# wrist_-_source.net
KiCad netlist of a schematic drawn in EAGLE
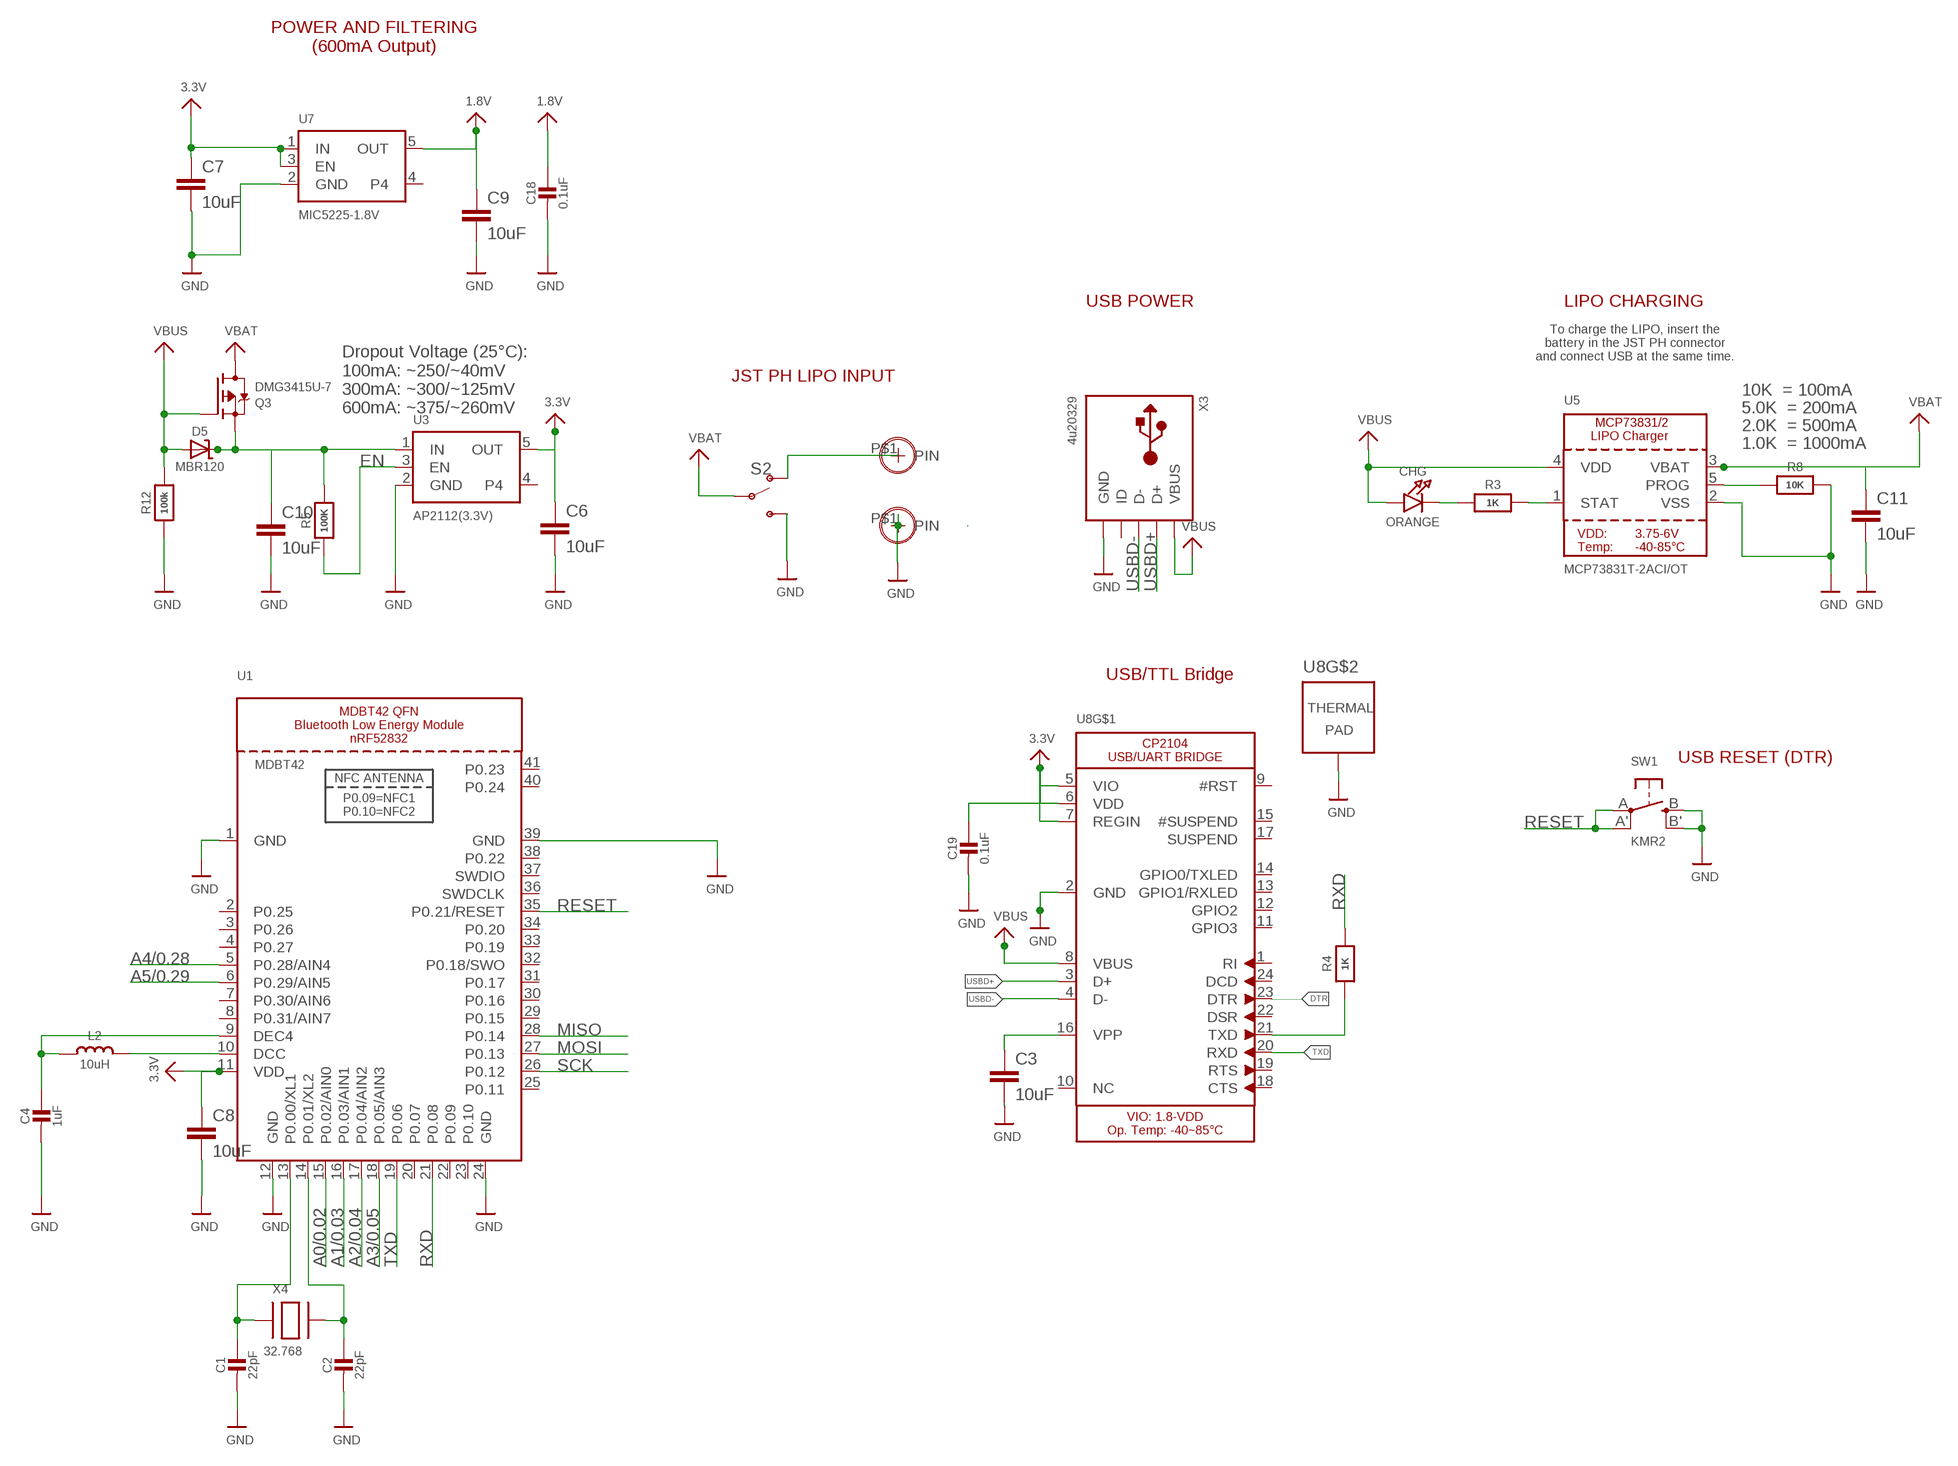
[diagram p0: schematic, sheet 1, part 1 of 2]
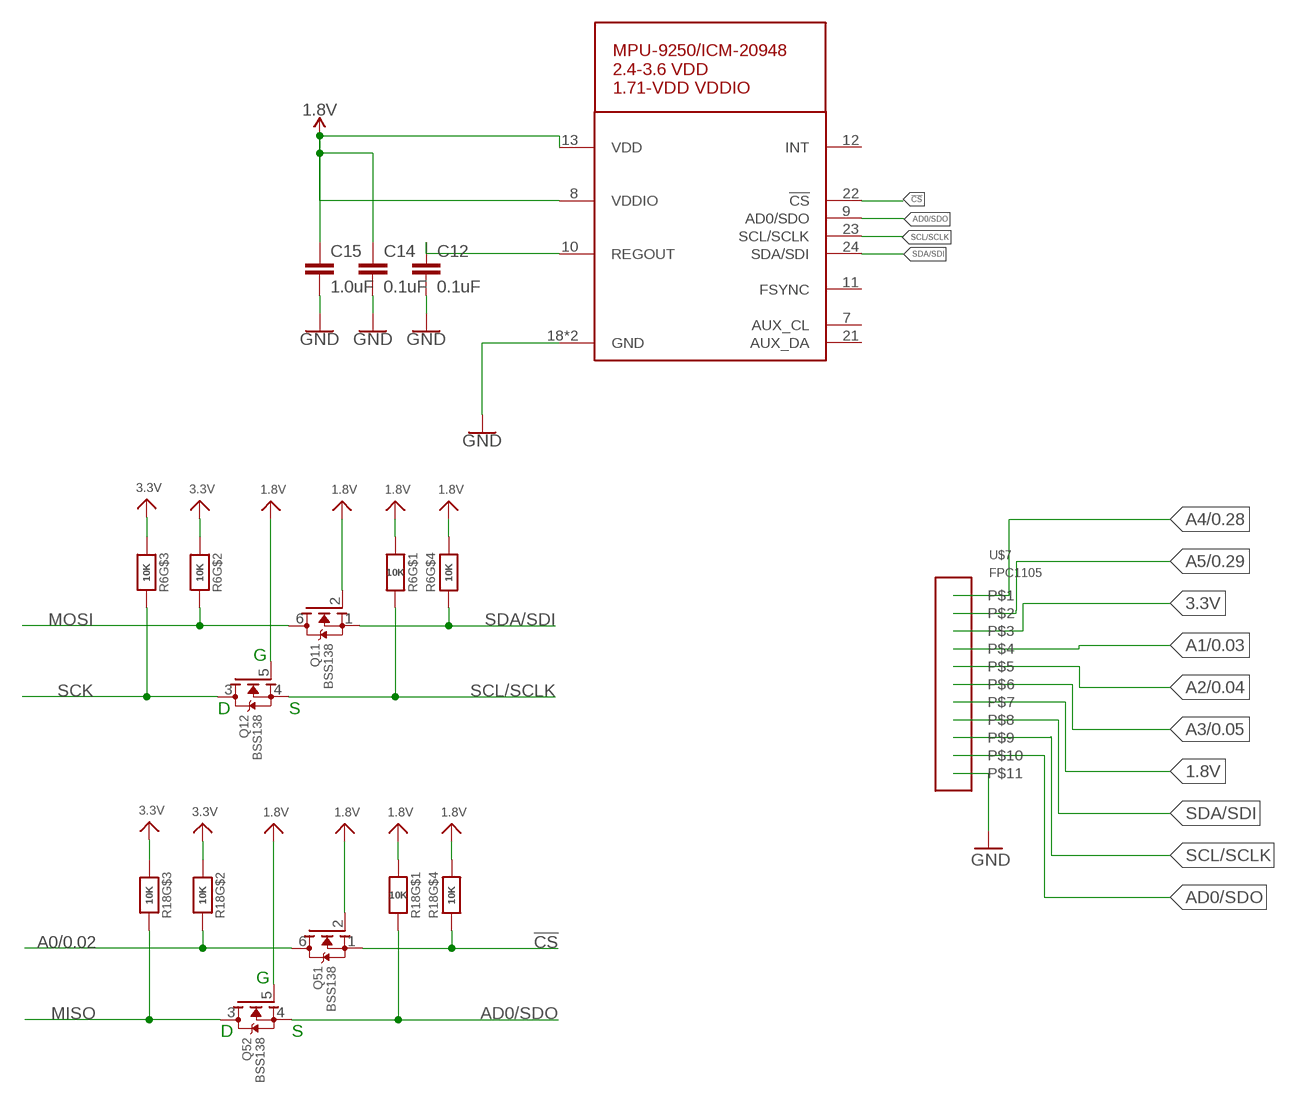
[diagram p1: schematic, sheet 1, part 2 of 2]

(export (version "E")
  (design (tool "Eeschema 10.0.6"))
  (components
    (comp (ref "C1")
      (value "22pF")
      (footprint "eagle-import:0603-NO")
      (libsource (lib "eagle-import") (part "CAP_CERAMIC0603_NO"))
    )
    (comp (ref "C2")
      (value "22pF")
      (footprint "eagle-import:0603-NO")
      (libsource (lib "eagle-import") (part "CAP_CERAMIC0603_NO"))
    )
    (comp (ref "C3")
      (value "10uF")
      (footprint "eagle-import:C0603")
      (libsource (lib "eagle-import") (part "C-EUC0603"))
    )
    (comp (ref "C4")
      (value "1uF")
      (footprint "eagle-import:0603-NO")
      (libsource (lib "eagle-import") (part "CAP_CERAMIC0603_NO"))
    )
    (comp (ref "C6")
      (value "10uF")
      (footprint "eagle-import:C0603")
      (libsource (lib "eagle-import") (part "C-EUC0603"))
    )
    (comp (ref "C7")
      (value "10uF")
      (footprint "eagle-import:C0603")
      (libsource (lib "eagle-import") (part "C-EUC0603"))
    )
    (comp (ref "C8")
      (value "10uF")
      (footprint "eagle-import:C0603")
      (libsource (lib "eagle-import") (part "C-EUC0603"))
    )
    (comp (ref "C9")
      (value "10uF")
      (footprint "eagle-import:C0603")
      (libsource (lib "eagle-import") (part "C-EUC0603"))
    )
    (comp (ref "C10")
      (value "10uF")
      (footprint "eagle-import:C0603")
      (libsource (lib "eagle-import") (part "C-EUC0603"))
    )
    (comp (ref "C11")
      (value "10uF")
      (footprint "eagle-import:C0603")
      (libsource (lib "eagle-import") (part "C-EUC0603"))
    )
    (comp (ref "C12")
      (value "0.1uF")
      (footprint "eagle-import:0603")
      (libsource (lib "eagle-import") (part "0.1UF-0603-25V-5%"))
    )
    (comp (ref "C14")
      (value "0.1uF")
      (footprint "eagle-import:0603")
      (libsource (lib "eagle-import") (part "0.1UF-0603-25V-5%"))
    )
    (comp (ref "C15")
      (value "1.0uF")
      (footprint "eagle-import:0603")
      (libsource (lib "eagle-import") (part "1.0UF-0603-16V-10%-X7R"))
    )
    (comp (ref "C18")
      (value "0.1uF")
      (footprint "eagle-import:0603-NO")
      (libsource (lib "eagle-import") (part "CAP_CERAMIC0603_NO"))
    )
    (comp (ref "C19")
      (value "0.1uF")
      (footprint "eagle-import:0603-NO")
      (libsource (lib "eagle-import") (part "CAP_CERAMIC0603_NO"))
    )
    (comp (ref "CHG")
      (value "ORANGE")
      (footprint "eagle-import:CHIPLED_0805_NOOUTLINE")
      (libsource (lib "eagle-import") (part "LED0805_NOOUTLINE"))
    )
    (comp (ref "D5")
      (value "MBR120")
      (footprint "eagle-import:SOD-123")
      (libsource (lib "eagle-import") (part "DIODE-SCHOTTKYSOD-123"))
    )
    (comp (ref "IC1")
      (value "ADAFRUIT_SENSOR_MPU-9250_ICM20948")
      (footprint "eagle-import:ADAFRUIT_SENSOR_QFN24_3MM_NOEP")
      (libsource (lib "eagle-import") (part "ADAFRUIT_SENSOR_MPU-9250_ICM20948"))
    )
    (comp (ref "L2")
      (value "10uH")
      (footprint "eagle-import:0805-NO")
      (libsource (lib "eagle-import") (part "INDUCTOR0805-NO"))
    )
    (comp (ref "Q1")
      (value "BSS138")
      (footprint "eagle-import:SOT363")
      (libsource (lib "eagle-import") (part "MOSFET-N_DUAL"))
    )
    (comp (ref "Q3")
      (value "DMG3415U-7")
      (footprint "eagle-import:SOT23-R")
      (libsource (lib "eagle-import") (part "MOSFET-P"))
    )
    (comp (ref "Q5")
      (value "BSS138")
      (footprint "eagle-import:SOT363")
      (libsource (lib "eagle-import") (part "MOSFET-N_DUAL"))
    )
    (comp (ref "R3")
      (value "1K")
      (footprint "eagle-import:0603-NO")
      (libsource (lib "eagle-import") (part "RESISTOR_0603_NOOUT"))
    )
    (comp (ref "R4")
      (value "1K")
      (footprint "eagle-import:0603-NO")
      (libsource (lib "eagle-import") (part "RESISTOR_0603_NOOUT"))
    )
    (comp (ref "R5")
      (value "100K")
      (footprint "eagle-import:0603-NO")
      (libsource (lib "eagle-import") (part "RESISTOR_0603_NOOUT"))
    )
    (comp (ref "R6")
      (value "10K")
      (footprint "eagle-import:RESPACK_4X0603")
      (libsource (lib "eagle-import") (part "RESISTOR_4PACK"))
    )
    (comp (ref "R8")
      (value "10K")
      (footprint "eagle-import:0603-NO")
      (libsource (lib "eagle-import") (part "RESISTOR_0603_NOOUT"))
    )
    (comp (ref "R12")
      (value "100k")
      (footprint "eagle-import:0603-NO")
      (libsource (lib "eagle-import") (part "RESISTOR_0603_NOOUT"))
    )
    (comp (ref "R18")
      (value "10K")
      (footprint "eagle-import:RESPACK_4X0603")
      (libsource (lib "eagle-import") (part "RESISTOR_4PACK"))
    )
    (comp (ref "S2")
      (value "SWITCH-SPDT-SMD-RIGHT-ANGLE")
      (footprint "eagle-import:SWITCH_SPST_SMD_A")
      (libsource (lib "eagle-import") (part "SWITCH-SPDT-SMD-RIGHT-ANGLE"))
    )
    (comp (ref "SW1")
      (value "KMR2")
      (footprint "eagle-import:BTN_KMR2_4.6X2.8")
      (libsource (lib "eagle-import") (part "SWITCH_TACT_SMT4.6X2.8"))
    )
    (comp (ref "U$7")
      (value "FPC1105")
      (footprint "eagle-import:FPC1105")
      (libsource (lib "eagle-import") (part "FPC1105"))
    )
    (comp (ref "U$9")
      (value "M3-HOLE_M0.9-HOLE0.9MM")
      (footprint "eagle-import:M3-HOLE_M0.9-HOLE")
      (libsource (lib "eagle-import") (part "M3-HOLE_M0.9-HOLE0.9MM"))
    )
    (comp (ref "U$13")
      (value "M3-HOLE_M0.9-HOLE0.9MM")
      (footprint "eagle-import:M3-HOLE_M0.9-HOLE")
      (libsource (lib "eagle-import") (part "M3-HOLE_M0.9-HOLE0.9MM"))
    )
    (comp (ref "U1")
      (value "MDBT42")
      (footprint "eagle-import:BLE_MODULE_RAYTAC_MDBT42")
      (libsource (lib "eagle-import") (part "NRF52832_MODULE_MDBT42"))
    )
    (comp (ref "U3")
      (value "AP2112(3.3V)")
      (footprint "eagle-import:SOT23-5")
      (libsource (lib "eagle-import") (part "VREG_SOT23-5"))
    )
    (comp (ref "U5")
      (value "MCP73831T-2ACI/OT")
      (footprint "eagle-import:SOT23-5")
      (libsource (lib "eagle-import") (part "MCP73831/2"))
    )
    (comp (ref "U7")
      (value "MIC5225-1.8V")
      (footprint "eagle-import:SOT23-5")
      (libsource (lib "eagle-import") (part "VREG_SOT23-5"))
    )
    (comp (ref "U8")
      (value "MICROBUILDER_CP2104")
      (footprint "eagle-import:MICROBUILDER_QFN24_4MM_SMSC")
      (libsource (lib "eagle-import") (part "MICROBUILDER_CP2104"))
    )
    (comp (ref "X3")
      (value "4u20329")
      (footprint "eagle-import:4UCONN_20329_V2")
      (libsource (lib "eagle-import") (part "USB_MICRO_20329_V2"))
    )
    (comp (ref "X4")
      (value "32.768")
      (footprint "eagle-import:XTAL3215")
      (libsource (lib "eagle-import") (part "XTAL-3.2X1.5"))
    )
  )
  (nets
    (net (code "1") (name "/A0{slash}0.02") (class "Default")
      (node (ref "Q5") (pin "6") (pinfunction "D_6") (pintype "bidirectional"))
      (node (ref "R18") (pin "7") (pinfunction "2_7") (pintype "passive"))
      (node (ref "U1") (pin "15") (pinfunction "P0.02/AIN0_15") (pintype "bidirectional"))
    )
    (net (code "2") (name "/EN") (class "Default")
      (node (ref "R5") (pin "1") (pinfunction "1_1") (pintype "passive"))
      (node (ref "U3") (pin "3") (pinfunction "EN_3") (pintype "input"))
    )
    (net (code "3") (name "/MISO") (class "Default")
      (node (ref "Q5") (pin "3") (pinfunction "D_3") (pintype "bidirectional"))
      (node (ref "R18") (pin "6") (pinfunction "2_6") (pintype "passive"))
      (node (ref "U1") (pin "28") (pinfunction "P0.14_28") (pintype "bidirectional"))
    )
    (net (code "4") (name "/MOSI") (class "Default")
      (node (ref "Q1") (pin "6") (pinfunction "D_6") (pintype "bidirectional"))
      (node (ref "R6") (pin "7") (pinfunction "2_7") (pintype "passive"))
      (node (ref "U1") (pin "27") (pinfunction "P0.13_27") (pintype "bidirectional"))
    )
    (net (code "5") (name "/RESET") (class "Default")
      (node (ref "SW1") (pin "A") (pinfunction "P_A") (pintype "passive"))
      (node (ref "SW1") (pin "A'") (pinfunction "P1_A'") (pintype "passive"))
      (node (ref "U1") (pin "35") (pinfunction "P0.21/RESET_35") (pintype "bidirectional"))
    )
    (net (code "6") (name "/RXD") (class "Default")
      (node (ref "R4") (pin "2") (pinfunction "2_2") (pintype "passive"))
      (node (ref "U1") (pin "21") (pinfunction "P0.08_21") (pintype "bidirectional"))
    )
    (net (code "7") (name "/SCK") (class "Default")
      (node (ref "Q1") (pin "3") (pinfunction "D_3") (pintype "bidirectional"))
      (node (ref "R6") (pin "6") (pinfunction "2_6") (pintype "passive"))
      (node (ref "U1") (pin "26") (pinfunction "P0.12_26") (pintype "bidirectional"))
    )
    (net (code "8") (name "/~{CS}") (class "Default")
      (node (ref "IC1") (pin "22") (pinfunction "~{CS}_22") (pintype "bidirectional"))
      (node (ref "Q5") (pin "1") (pinfunction "S_1") (pintype "bidirectional"))
      (node (ref "R18") (pin "5") (pinfunction "2_5") (pintype "passive"))
    )
    (net (code "9") (name "1.8V") (class "Default")
      (node (ref "C14") (pin "1") (pinfunction "1_1") (pintype "passive"))
      (node (ref "C15") (pin "1") (pinfunction "1_1") (pintype "passive"))
      (node (ref "C18") (pin "1") (pinfunction "1_1") (pintype "passive"))
      (node (ref "C9") (pin "1") (pinfunction "1_1") (pintype "passive"))
      (node (ref "IC1") (pin "13") (pinfunction "VDD_13") (pintype "bidirectional"))
      (node (ref "IC1") (pin "8") (pinfunction "VDDIO_8") (pintype "bidirectional"))
      (node (ref "Q1") (pin "2") (pinfunction "G_2") (pintype "bidirectional"))
      (node (ref "Q1") (pin "5") (pinfunction "G_5") (pintype "bidirectional"))
      (node (ref "Q5") (pin "2") (pinfunction "G_2") (pintype "bidirectional"))
      (node (ref "Q5") (pin "5") (pinfunction "G_5") (pintype "bidirectional"))
      (node (ref "R18") (pin "4") (pinfunction "1_4") (pintype "passive"))
      (node (ref "R18") (pin "8") (pinfunction "2_8") (pintype "passive"))
      (node (ref "R6") (pin "4") (pinfunction "1_4") (pintype "passive"))
      (node (ref "R6") (pin "8") (pinfunction "2_8") (pintype "passive"))
      (node (ref "U$7") (pin "P$7") (pinfunction "P$7_P$7") (pintype "bidirectional"))
      (node (ref "U7") (pin "5") (pinfunction "OUT_5") (pintype "power_in"))
    )
    (net (code "10") (name "3.3V") (class "Default")
      (node (ref "C19") (pin "1") (pinfunction "1_1") (pintype "passive"))
      (node (ref "C6") (pin "1") (pinfunction "1_1") (pintype "passive"))
      (node (ref "C7") (pin "1") (pinfunction "1_1") (pintype "passive"))
      (node (ref "C8") (pin "1") (pinfunction "1_1") (pintype "passive"))
      (node (ref "R18") (pin "2") (pinfunction "1_2") (pintype "passive"))
      (node (ref "R18") (pin "3") (pinfunction "1_3") (pintype "passive"))
      (node (ref "R6") (pin "2") (pinfunction "1_2") (pintype "passive"))
      (node (ref "R6") (pin "3") (pinfunction "1_3") (pintype "passive"))
      (node (ref "U$7") (pin "P$3") (pinfunction "P$3_P$3") (pintype "bidirectional"))
      (node (ref "U1") (pin "11") (pinfunction "VDD_11") (pintype "bidirectional"))
      (node (ref "U3") (pin "5") (pinfunction "OUT_5") (pintype "power_in"))
      (node (ref "U7") (pin "1") (pinfunction "IN_1") (pintype "power_in"))
      (node (ref "U7") (pin "3") (pinfunction "EN_3") (pintype "input"))
      (node (ref "U8") (pin "5") (pinfunction "VIO_5") (pintype "power_in"))
      (node (ref "U8") (pin "6") (pinfunction "VDD_6") (pintype "power_in"))
      (node (ref "U8") (pin "7") (pinfunction "REGIN_7") (pintype "power_in"))
    )
    (net (code "11") (name "A1{slash}0.03") (class "Default")
      (node (ref "U$7") (pin "P$4") (pinfunction "P$4_P$4") (pintype "bidirectional"))
      (node (ref "U1") (pin "16") (pinfunction "P0.03/AIN1_16") (pintype "bidirectional"))
    )
    (net (code "12") (name "A2{slash}0.04") (class "Default")
      (node (ref "U$7") (pin "P$5") (pinfunction "P$5_P$5") (pintype "bidirectional"))
      (node (ref "U1") (pin "17") (pinfunction "P0.04/AIN2_17") (pintype "bidirectional"))
    )
    (net (code "13") (name "A3{slash}0.05") (class "Default")
      (node (ref "U$7") (pin "P$6") (pinfunction "P$6_P$6") (pintype "bidirectional"))
      (node (ref "U1") (pin "18") (pinfunction "P0.05/AIN3_18") (pintype "bidirectional"))
    )
    (net (code "14") (name "A4{slash}0.28") (class "Default")
      (node (ref "U$7") (pin "P$1") (pinfunction "P$1_P$1") (pintype "bidirectional"))
      (node (ref "U1") (pin "5") (pinfunction "P0.28/AIN4_5") (pintype "bidirectional"))
    )
    (net (code "15") (name "A5{slash}0.29") (class "Default")
      (node (ref "U$7") (pin "P$2") (pinfunction "P$2_P$2") (pintype "bidirectional"))
      (node (ref "U1") (pin "6") (pinfunction "P0.29/AIN5_6") (pintype "bidirectional"))
    )
    (net (code "16") (name "AD0{slash}SDO") (class "Default")
      (node (ref "IC1") (pin "9") (pinfunction "AD0/SDO_9") (pintype "bidirectional"))
      (node (ref "Q5") (pin "4") (pinfunction "S_4") (pintype "bidirectional"))
      (node (ref "R18") (pin "1") (pinfunction "1_1") (pintype "passive"))
      (node (ref "U$7") (pin "P$10") (pinfunction "P$10_P$10") (pintype "bidirectional"))
    )
    (net (code "17") (name "DTR") (class "Default")
      (node (ref "U8") (pin "23") (pinfunction "DTR_23") (pintype "output"))
    )
    (net (code "18") (name "GND") (class "Default")
      (node (ref "C1") (pin "2") (pinfunction "2_2") (pintype "passive"))
      (node (ref "C10") (pin "2") (pinfunction "2_2") (pintype "passive"))
      (node (ref "C11") (pin "2") (pinfunction "2_2") (pintype "passive"))
      (node (ref "C12") (pin "2") (pinfunction "2_2") (pintype "passive"))
      (node (ref "C14") (pin "2") (pinfunction "2_2") (pintype "passive"))
      (node (ref "C15") (pin "2") (pinfunction "2_2") (pintype "passive"))
      (node (ref "C18") (pin "2") (pinfunction "2_2") (pintype "passive"))
      (node (ref "C19") (pin "2") (pinfunction "2_2") (pintype "passive"))
      (node (ref "C2") (pin "2") (pinfunction "2_2") (pintype "passive"))
      (node (ref "C3") (pin "2") (pinfunction "2_2") (pintype "passive"))
      (node (ref "C4") (pin "2") (pinfunction "2_2") (pintype "passive"))
      (node (ref "C6") (pin "2") (pinfunction "2_2") (pintype "passive"))
      (node (ref "C7") (pin "2") (pinfunction "2_2") (pintype "passive"))
      (node (ref "C8") (pin "2") (pinfunction "2_2") (pintype "passive"))
      (node (ref "C9") (pin "2") (pinfunction "2_2") (pintype "passive"))
      (node (ref "IC1") (pin "18") (pinfunction "GND_18") (pintype "bidirectional"))
      (node (ref "IC1") (pin "20") (pinfunction "GND_20") (pintype "bidirectional"))
      (node (ref "R12") (pin "1") (pinfunction "1_1") (pintype "passive"))
      (node (ref "R8") (pin "2") (pinfunction "2_2") (pintype "passive"))
      (node (ref "S2") (pin "3") (pinfunction "S_3") (pintype "passive"))
      (node (ref "SW1") (pin "B") (pinfunction "S_B") (pintype "passive"))
      (node (ref "SW1") (pin "B'") (pinfunction "S1_B'") (pintype "passive"))
      (node (ref "U$13") (pin "P$1") (pinfunction "PIN_P$1") (pintype "bidirectional"))
      (node (ref "U$7") (pin "P$11") (pinfunction "P$11_P$11") (pintype "bidirectional"))
      (node (ref "U1") (pin "1") (pinfunction "GND_1") (pintype "bidirectional"))
      (node (ref "U1") (pin "12") (pinfunction "GND_12") (pintype "bidirectional"))
      (node (ref "U1") (pin "24") (pinfunction "GND_24") (pintype "bidirectional"))
      (node (ref "U1") (pin "39") (pinfunction "GND_39") (pintype "bidirectional"))
      (node (ref "U3") (pin "2") (pinfunction "GND_2") (pintype "power_in"))
      (node (ref "U5") (pin "2") (pinfunction "VSS_2") (pintype "power_in"))
      (node (ref "U7") (pin "2") (pinfunction "GND_2") (pintype "power_in"))
      (node (ref "U8") (pin "2") (pinfunction "GND_2") (pintype "power_in"))
      (node (ref "U8") (pin "THERM") (pinfunction "TP_THERM") (pintype "power_in"))
      (node (ref "X3") (pin "BASE@1") (pinfunction "GND_BASE@1") (pintype "power_in"))
      (node (ref "X3") (pin "BASE@2") (pinfunction "GND_BASE@2") (pintype "power_in"))
      (node (ref "X3") (pin "GND") (pinfunction "GND_GND") (pintype "power_in"))
      (node (ref "X3") (pin "SPRT@1") (pinfunction "GND_SPRT@1") (pintype "power_in"))
      (node (ref "X3") (pin "SPRT@2") (pinfunction "GND_SPRT@2") (pintype "power_in"))
      (node (ref "X3") (pin "SPRT@3") (pinfunction "GND_SPRT@3") (pintype "power_in"))
      (node (ref "X3") (pin "SPRT@4") (pinfunction "GND_SPRT@4") (pintype "power_in"))
    )
    (net (code "19") (name "Net-(CHG-PadC)") (class "Default")
      (node (ref "CHG") (pin "C") (pinfunction "C_C") (pintype "passive"))
      (node (ref "R3") (pin "1") (pinfunction "1_1") (pintype "passive"))
    )
    (net (code "20") (name "Net-(IC1-REGOUT)") (class "Default")
      (node (ref "C12") (pin "1") (pinfunction "1_1") (pintype "passive"))
      (node (ref "IC1") (pin "10") (pinfunction "REGOUT_10") (pintype "bidirectional"))
    )
    (net (code "21") (name "Net-(Q3-S)") (class "Default")
      (node (ref "C10") (pin "1") (pinfunction "1_1") (pintype "passive"))
      (node (ref "D5") (pin "C") (pinfunction "C_C") (pintype "passive"))
      (node (ref "Q3") (pin "2") (pinfunction "S_2") (pintype "passive"))
      (node (ref "R5") (pin "2") (pinfunction "2_2") (pintype "passive"))
      (node (ref "U3") (pin "1") (pinfunction "IN_1") (pintype "power_in"))
    )
    (net (code "22") (name "Net-(S2-O)") (class "Default")
      (node (ref "S2") (pin "1") (pinfunction "O_1") (pintype "passive"))
      (node (ref "U$9") (pin "P$1") (pinfunction "PIN_P$1") (pintype "bidirectional"))
    )
    (net (code "23") (name "Net-(U1-DCC)") (class "Default")
      (node (ref "L2") (pin "2") (pinfunction "2_2") (pintype "passive"))
      (node (ref "U1") (pin "10") (pinfunction "DCC_10") (pintype "bidirectional"))
    )
    (net (code "24") (name "Net-(U1-DEC4)") (class "Default")
      (node (ref "C4") (pin "1") (pinfunction "1_1") (pintype "passive"))
      (node (ref "L2") (pin "1") (pinfunction "1_1") (pintype "passive"))
      (node (ref "U1") (pin "9") (pinfunction "DEC4_9") (pintype "bidirectional"))
    )
    (net (code "25") (name "Net-(U1-P0.00{slash}XL1)") (class "Default")
      (node (ref "C1") (pin "1") (pinfunction "1_1") (pintype "passive"))
      (node (ref "U1") (pin "13") (pinfunction "P0.00/XL1_13") (pintype "bidirectional"))
      (node (ref "X4") (pin "P$1") (pinfunction "P$1_P$1") (pintype "bidirectional"))
    )
    (net (code "26") (name "Net-(U1-P0.01{slash}XL2)") (class "Default")
      (node (ref "C2") (pin "1") (pinfunction "1_1") (pintype "passive"))
      (node (ref "U1") (pin "14") (pinfunction "P0.01/XL2_14") (pintype "bidirectional"))
      (node (ref "X4") (pin "P$2") (pinfunction "P$2_P$2") (pintype "bidirectional"))
    )
    (net (code "27") (name "Net-(U5-PROG)") (class "Default")
      (node (ref "R8") (pin "1") (pinfunction "1_1") (pintype "passive"))
      (node (ref "U5") (pin "5") (pinfunction "PROG_5") (pintype "input"))
    )
    (net (code "28") (name "Net-(U5-STAT)") (class "Default")
      (node (ref "R3") (pin "2") (pinfunction "2_2") (pintype "passive"))
      (node (ref "U5") (pin "1") (pinfunction "STAT_1") (pintype "output"))
    )
    (net (code "29") (name "Net-(U8A-TXD)") (class "Default")
      (node (ref "R4") (pin "1") (pinfunction "1_1") (pintype "passive"))
      (node (ref "U8") (pin "21") (pinfunction "TXD_21") (pintype "output"))
    )
    (net (code "30") (name "Net-(U8A-VPP)") (class "Default")
      (node (ref "C3") (pin "1") (pinfunction "1_1") (pintype "passive"))
      (node (ref "U8") (pin "16") (pinfunction "VPP_16") (pintype "bidirectional"))
    )
    (net (code "31") (name "SCL{slash}SCLK") (class "Default")
      (node (ref "IC1") (pin "23") (pinfunction "SCL/SCLK_23") (pintype "bidirectional"))
      (node (ref "Q1") (pin "4") (pinfunction "S_4") (pintype "bidirectional"))
      (node (ref "R6") (pin "1") (pinfunction "1_1") (pintype "passive"))
      (node (ref "U$7") (pin "P$9") (pinfunction "P$9_P$9") (pintype "bidirectional"))
    )
    (net (code "32") (name "SDA{slash}SDI") (class "Default")
      (node (ref "IC1") (pin "24") (pinfunction "SDA/SDI_24") (pintype "bidirectional"))
      (node (ref "Q1") (pin "1") (pinfunction "S_1") (pintype "bidirectional"))
      (node (ref "R6") (pin "5") (pinfunction "2_5") (pintype "passive"))
      (node (ref "U$7") (pin "P$8") (pinfunction "P$8_P$8") (pintype "bidirectional"))
    )
    (net (code "33") (name "TXD") (class "Default")
      (node (ref "U1") (pin "19") (pinfunction "P0.06_19") (pintype "bidirectional"))
      (node (ref "U8") (pin "20") (pinfunction "RXD_20") (pintype "input"))
    )
    (net (code "34") (name "USBD+") (class "Default")
      (node (ref "U8") (pin "3") (pinfunction "D+_3") (pintype "bidirectional"))
      (node (ref "X3") (pin "D+") (pinfunction "D+_D+") (pintype "bidirectional"))
    )
    (net (code "35") (name "USBD-") (class "Default")
      (node (ref "U8") (pin "4") (pinfunction "D-_4") (pintype "bidirectional"))
      (node (ref "X3") (pin "D-") (pinfunction "D-_D-") (pintype "bidirectional"))
    )
    (net (code "36") (name "VBAT") (class "Default")
      (node (ref "C11") (pin "1") (pinfunction "1_1") (pintype "passive"))
      (node (ref "Q3") (pin "3") (pinfunction "D_3") (pintype "passive"))
      (node (ref "S2") (pin "2") (pinfunction "P_2") (pintype "passive"))
      (node (ref "U5") (pin "3") (pinfunction "VBAT_3") (pintype "power_in"))
    )
    (net (code "37") (name "VBUS") (class "Default")
      (node (ref "CHG") (pin "A") (pinfunction "A_A") (pintype "passive"))
      (node (ref "D5") (pin "A") (pinfunction "A_A") (pintype "passive"))
      (node (ref "Q3") (pin "1") (pinfunction "G_1") (pintype "passive"))
      (node (ref "R12") (pin "2") (pinfunction "2_2") (pintype "passive"))
      (node (ref "U5") (pin "4") (pinfunction "VDD_4") (pintype "power_in"))
      (node (ref "U8") (pin "8") (pinfunction "VBUS_8") (pintype "power_in"))
      (node (ref "X3") (pin "VBUS") (pinfunction "VBUS_VBUS") (pintype "power_in"))
    )
    (net (code "38") (name "unconnected-(IC1-AUX_CL-Pad7)") (class "Default")
      (node (ref "IC1") (pin "7") (pinfunction "AUX_CL_7") (pintype "bidirectional"))
    )
    (net (code "39") (name "unconnected-(IC1-AUX_DA-Pad21)") (class "Default")
      (node (ref "IC1") (pin "21") (pinfunction "AUX_DA_21") (pintype "bidirectional"))
    )
    (net (code "40") (name "unconnected-(IC1-FSYNC-Pad11)") (class "Default")
      (node (ref "IC1") (pin "11") (pinfunction "FSYNC_11") (pintype "bidirectional"))
    )
    (net (code "41") (name "unconnected-(IC1-INT-Pad12)") (class "Default")
      (node (ref "IC1") (pin "12") (pinfunction "INT_12") (pintype "bidirectional"))
    )
    (net (code "42") (name "unconnected-(U1-P0.07-Pad20)") (class "Default")
      (node (ref "U1") (pin "20") (pinfunction "P0.07_20") (pintype "bidirectional"))
    )
    (net (code "43") (name "unconnected-(U1-P0.09-Pad22)") (class "Default")
      (node (ref "U1") (pin "22") (pinfunction "P0.09_22") (pintype "bidirectional"))
    )
    (net (code "44") (name "unconnected-(U1-P0.10-Pad23)") (class "Default")
      (node (ref "U1") (pin "23") (pinfunction "P0.10_23") (pintype "bidirectional"))
    )
    (net (code "45") (name "unconnected-(U1-P0.11-Pad25)") (class "Default")
      (node (ref "U1") (pin "25") (pinfunction "P0.11_25") (pintype "bidirectional"))
    )
    (net (code "46") (name "unconnected-(U1-P0.15-Pad29)") (class "Default")
      (node (ref "U1") (pin "29") (pinfunction "P0.15_29") (pintype "bidirectional"))
    )
    (net (code "47") (name "unconnected-(U1-P0.16-Pad30)") (class "Default")
      (node (ref "U1") (pin "30") (pinfunction "P0.16_30") (pintype "bidirectional"))
    )
    (net (code "48") (name "unconnected-(U1-P0.17-Pad31)") (class "Default")
      (node (ref "U1") (pin "31") (pinfunction "P0.17_31") (pintype "bidirectional"))
    )
    (net (code "49") (name "unconnected-(U1-P0.18{slash}SWO-Pad32)") (class "Default")
      (node (ref "U1") (pin "32") (pinfunction "P0.18/SWO_32") (pintype "bidirectional"))
    )
    (net (code "50") (name "unconnected-(U1-P0.19-Pad33)") (class "Default")
      (node (ref "U1") (pin "33") (pinfunction "P0.19_33") (pintype "bidirectional"))
    )
    (net (code "51") (name "unconnected-(U1-P0.20-Pad34)") (class "Default")
      (node (ref "U1") (pin "34") (pinfunction "P0.20_34") (pintype "bidirectional"))
    )
    (net (code "52") (name "unconnected-(U1-P0.22-Pad38)") (class "Default")
      (node (ref "U1") (pin "38") (pinfunction "P0.22_38") (pintype "bidirectional"))
    )
    (net (code "53") (name "unconnected-(U1-P0.23-Pad41)") (class "Default")
      (node (ref "U1") (pin "41") (pinfunction "P0.23_41") (pintype "bidirectional"))
    )
    (net (code "54") (name "unconnected-(U1-P0.24-Pad40)") (class "Default")
      (node (ref "U1") (pin "40") (pinfunction "P0.24_40") (pintype "bidirectional"))
    )
    (net (code "55") (name "unconnected-(U1-P0.25-Pad2)") (class "Default")
      (node (ref "U1") (pin "2") (pinfunction "P0.25_2") (pintype "bidirectional"))
    )
    (net (code "56") (name "unconnected-(U1-P0.26-Pad3)") (class "Default")
      (node (ref "U1") (pin "3") (pinfunction "P0.26_3") (pintype "bidirectional"))
    )
    (net (code "57") (name "unconnected-(U1-P0.27-Pad4)") (class "Default")
      (node (ref "U1") (pin "4") (pinfunction "P0.27_4") (pintype "bidirectional"))
    )
    (net (code "58") (name "unconnected-(U1-P0.30{slash}AIN6-Pad7)") (class "Default")
      (node (ref "U1") (pin "7") (pinfunction "P0.30/AIN6_7") (pintype "bidirectional"))
    )
    (net (code "59") (name "unconnected-(U1-P0.31{slash}AIN7-Pad8)") (class "Default")
      (node (ref "U1") (pin "8") (pinfunction "P0.31/AIN7_8") (pintype "bidirectional"))
    )
    (net (code "60") (name "unconnected-(U1-SWDCLK-Pad36)") (class "Default")
      (node (ref "U1") (pin "36") (pinfunction "SWDCLK_36") (pintype "bidirectional"))
    )
    (net (code "61") (name "unconnected-(U1-SWDIO-Pad37)") (class "Default")
      (node (ref "U1") (pin "37") (pinfunction "SWDIO_37") (pintype "bidirectional"))
    )
    (net (code "62") (name "unconnected-(U3-P4-Pad4)") (class "Default")
      (node (ref "U3") (pin "4") (pinfunction "P4_4") (pintype "bidirectional"))
    )
    (net (code "63") (name "unconnected-(U7-P4-Pad4)") (class "Default")
      (node (ref "U7") (pin "4") (pinfunction "P4_4") (pintype "bidirectional"))
    )
    (net (code "64") (name "unconnected-(U8A-#RST-Pad9)") (class "Default")
      (node (ref "U8") (pin "9") (pinfunction "#RST_9") (pintype "bidirectional"))
    )
    (net (code "65") (name "unconnected-(U8A-#SUSPEND-Pad15)") (class "Default")
      (node (ref "U8") (pin "15") (pinfunction "#SUSPEND_15") (pintype "output"))
    )
    (net (code "66") (name "unconnected-(U8A-CTS-Pad18)") (class "Default")
      (node (ref "U8") (pin "18") (pinfunction "CTS_18") (pintype "input"))
    )
    (net (code "67") (name "unconnected-(U8A-DCD-Pad24)") (class "Default")
      (node (ref "U8") (pin "24") (pinfunction "DCD_24") (pintype "input"))
    )
    (net (code "68") (name "unconnected-(U8A-DSR-Pad22)") (class "Default")
      (node (ref "U8") (pin "22") (pinfunction "DSR_22") (pintype "input"))
    )
    (net (code "69") (name "unconnected-(U8A-GPIO0{slash}TXLED-Pad14)") (class "Default")
      (node (ref "U8") (pin "14") (pinfunction "GPIO0/TXLED_14") (pintype "bidirectional"))
    )
    (net (code "70") (name "unconnected-(U8A-GPIO1{slash}RXLED-Pad13)") (class "Default")
      (node (ref "U8") (pin "13") (pinfunction "GPIO1/RXLED_13") (pintype "bidirectional"))
    )
    (net (code "71") (name "unconnected-(U8A-GPIO2-Pad12)") (class "Default")
      (node (ref "U8") (pin "12") (pinfunction "GPIO2_12") (pintype "bidirectional"))
    )
    (net (code "72") (name "unconnected-(U8A-GPIO3-Pad11)") (class "Default")
      (node (ref "U8") (pin "11") (pinfunction "GPIO3_11") (pintype "bidirectional"))
    )
    (net (code "73") (name "unconnected-(U8A-NC-Pad10)") (class "Default")
      (node (ref "U8") (pin "10") (pinfunction "NC_10") (pintype "no_connect"))
    )
    (net (code "74") (name "unconnected-(U8A-RI-Pad1)") (class "Default")
      (node (ref "U8") (pin "1") (pinfunction "RI_1") (pintype "input"))
    )
    (net (code "75") (name "unconnected-(U8A-RTS-Pad19)") (class "Default")
      (node (ref "U8") (pin "19") (pinfunction "RTS_19") (pintype "output"))
    )
    (net (code "76") (name "unconnected-(U8A-SUSPEND-Pad17)") (class "Default")
      (node (ref "U8") (pin "17") (pinfunction "SUSPEND_17") (pintype "output"))
    )
    (net (code "77") (name "unconnected-(X3-PadID)") (class "Default")
      (node (ref "X3") (pin "ID") (pinfunction "ID_ID") (pintype "bidirectional"))
    )
  )
)
